# Slave.net
KiCad netlist of a schematic drawn in Altium Designer
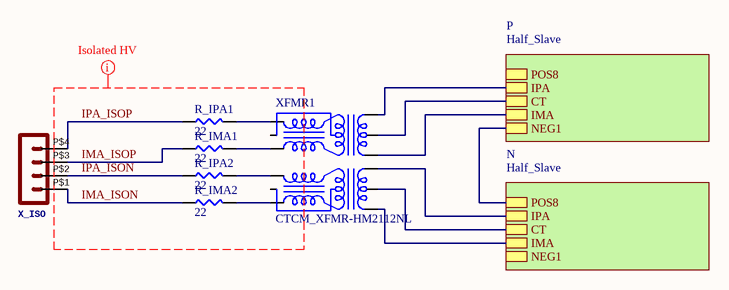
[diagram p0: Slave.SchDoc]

(export (version "E")
  (design (tool "Eeschema 10.0.6"))
  (components
    (comp (ref "R_IMA1")
      (value "22")
      (footprint "RES-0603")
      (libsource (lib "ife19_Elec_Library") (part "RES-0603"))
    )
    (comp (ref "R_IMA2")
      (value "22")
      (footprint "RES-0603")
      (libsource (lib "ife19_Elec_Library") (part "RES-0603"))
    )
    (comp (ref "R_IPA1")
      (value "22")
      (footprint "RES-0603")
      (libsource (lib "ife19_Elec_Library") (part "RES-0603"))
    )
    (comp (ref "R_IPA2")
      (value "22")
      (footprint "RES-0603")
      (libsource (lib "ife19_Elec_Library") (part "RES-0603"))
    )
    (comp (ref "XFMR1")
      (value "CTCM_XFMR-HM2112NL")
      (footprint "HM2112NL")
      (libsource (lib "ife19_Elec_Library") (part "CTCM_XFMR-HM2112NL"))
    )
    (comp (ref "X_ISO")
      (value "Molex - Micro-Fit 3.0 Series connector,  3.00mm (0.118\") pitch header, 4 positions.")
      (footprint "43650-0424")
      (libsource (lib "ife19_Elec_Conn_Library") (part "POS4_MF43650-0424"))
    )
  )
  (nets
    (net (code "1") (name "/CT") (class "Default")
      (node (ref "XFMR1") (pin "5") (pinfunction "5_5") (pintype "passive"))
    )
    (net (code "2") (name "/CT_1") (class "Default")
      (node (ref "XFMR1") (pin "2") (pinfunction "2_2") (pintype "passive"))
    )
    (net (code "3") (name "/IMA") (class "Default")
      (node (ref "XFMR1") (pin "4") (pinfunction "4_4") (pintype "passive"))
    )
    (net (code "4") (name "/IMA_1") (class "Default")
      (node (ref "XFMR1") (pin "1") (pinfunction "1_1") (pintype "passive"))
    )
    (net (code "5") (name "/IMA_ISON") (class "Default")
      (node (ref "R_IMA2") (pin "1") (pinfunction "1_1") (pintype "passive"))
      (node (ref "X_ISO") (pin "P$1") (pinfunction "1_P$1") (pintype "passive"))
    )
    (net (code "6") (name "/IMA_ISOP") (class "Default")
      (node (ref "R_IMA1") (pin "1") (pinfunction "1_1") (pintype "passive"))
      (node (ref "X_ISO") (pin "P$3") (pinfunction "3_P$3") (pintype "passive"))
    )
    (net (code "7") (name "/IPA") (class "Default")
      (node (ref "XFMR1") (pin "6") (pinfunction "6_6") (pintype "passive"))
    )
    (net (code "8") (name "/IPA_1") (class "Default")
      (node (ref "XFMR1") (pin "3") (pinfunction "3_3") (pintype "passive"))
    )
    (net (code "9") (name "/IPA_ISON") (class "Default")
      (node (ref "R_IPA2") (pin "1") (pinfunction "1_1") (pintype "passive"))
      (node (ref "X_ISO") (pin "P$2") (pinfunction "2_P$2") (pintype "passive"))
    )
    (net (code "10") (name "/IPA_ISOP") (class "Default")
      (node (ref "R_IPA1") (pin "1") (pinfunction "1_1") (pintype "passive"))
      (node (ref "X_ISO") (pin "P$4") (pinfunction "4_P$4") (pintype "passive"))
    )
    (net (code "14") (name "Net-(R_IMA1-Pad2)") (class "Default")
      (node (ref "R_IMA1") (pin "2") (pinfunction "2_2") (pintype "passive"))
      (node (ref "XFMR1") (pin "9") (pinfunction "9_9") (pintype "passive"))
    )
    (net (code "15") (name "Net-(R_IMA2-Pad2)") (class "Default")
      (node (ref "R_IMA2") (pin "2") (pinfunction "2_2") (pintype "passive"))
      (node (ref "XFMR1") (pin "12") (pinfunction "12_12") (pintype "passive"))
    )
    (net (code "16") (name "Net-(R_IPA1-Pad2)") (class "Default")
      (node (ref "R_IPA1") (pin "2") (pinfunction "2_2") (pintype "passive"))
      (node (ref "XFMR1") (pin "7") (pinfunction "7_7") (pintype "passive"))
    )
    (net (code "17") (name "Net-(R_IPA2-Pad2)") (class "Default")
      (node (ref "R_IPA2") (pin "2") (pinfunction "2_2") (pintype "passive"))
      (node (ref "XFMR1") (pin "10") (pinfunction "10_10") (pintype "passive"))
    )
    (net (code "18") (name "unconnected-(XFMR1-Pad8)") (class "Default")
      (node (ref "XFMR1") (pin "8") (pinfunction "8_8") (pintype "passive"))
    )
    (net (code "19") (name "unconnected-(XFMR1-Pad11)") (class "Default")
      (node (ref "XFMR1") (pin "11") (pinfunction "11_11") (pintype "passive"))
    )
  )
)
